# MainBoard_V100_PSU_AFE.net
KiCad netlist of a schematic drawn in Altium Designer
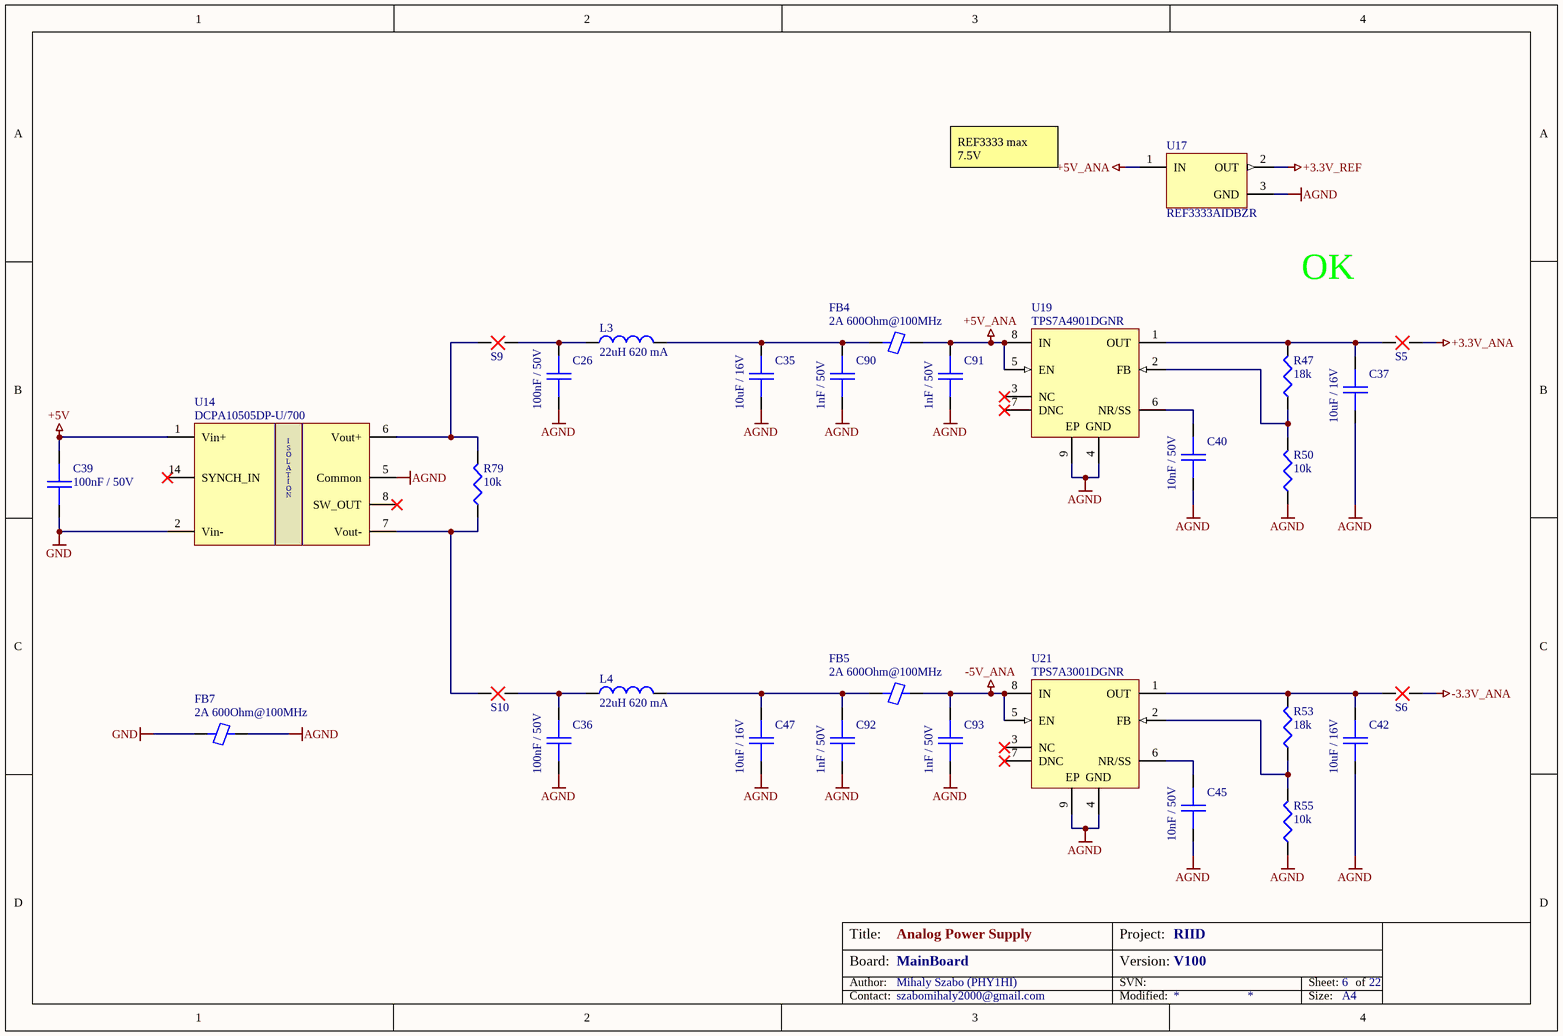
[diagram p0: MainBoard_V100_PSU_AFE.SchDoc]

(export (version "E")
  (design (tool "Eeschema 10.0.6"))
  (components
    (comp (ref "C26")
      (value "100nF / 50V")
      (footprint "0805_C")
      (description "100nF 50V X7R")
      (fields (field (name "PART NUMBER") "SMD0805-100nF-50V"))
      (libsource (lib "ALTIUM_DB_LIB") (part "CAP_NONPOL"))
    )
    (comp (ref "C35")
      (value "10uF / 16V")
      (footprint "0805_C")
      (description "10uF 16V X5R")
      (fields (field (name "PART NUMBER") "SMD0805-10uF-16V"))
      (libsource (lib "ALTIUM_DB_LIB") (part "CAP_NONPOL"))
    )
    (comp (ref "C36")
      (value "100nF / 50V")
      (footprint "0805_C")
      (description "100nF 50V X7R")
      (fields (field (name "PART NUMBER") "SMD0805-100nF-50V"))
      (libsource (lib "ALTIUM_DB_LIB") (part "CAP_NONPOL"))
    )
    (comp (ref "C37")
      (value "10uF / 16V")
      (footprint "0805_C")
      (description "10uF 16V X5R")
      (fields (field (name "PART NUMBER") "SMD0805-10uF-16V"))
      (libsource (lib "ALTIUM_DB_LIB") (part "CAP_NONPOL"))
    )
    (comp (ref "C39")
      (value "100nF / 50V")
      (footprint "0805_C")
      (description "100nF 50V X7R")
      (fields (field (name "PART NUMBER") "SMD0805-100nF-50V"))
      (libsource (lib "ALTIUM_DB_LIB") (part "CAP_NONPOL"))
    )
    (comp (ref "C40")
      (value "10nF / 50V")
      (footprint "0805_C")
      (description "10nF 50V X7R")
      (fields (field (name "PART NUMBER") "SMD0805-10nF-50V"))
      (libsource (lib "ALTIUM_DB_LIB") (part "CAP_NONPOL"))
    )
    (comp (ref "C42")
      (value "10uF / 16V")
      (footprint "0805_C")
      (description "10uF 16V X5R")
      (fields (field (name "PART NUMBER") "SMD0805-10uF-16V"))
      (libsource (lib "ALTIUM_DB_LIB") (part "CAP_NONPOL"))
    )
    (comp (ref "C45")
      (value "10nF / 50V")
      (footprint "0805_C")
      (description "10nF 50V X7R")
      (fields (field (name "PART NUMBER") "SMD0805-10nF-50V"))
      (libsource (lib "ALTIUM_DB_LIB") (part "CAP_NONPOL"))
    )
    (comp (ref "C47")
      (value "10uF / 16V")
      (footprint "0805_C")
      (description "10uF 16V X5R")
      (fields (field (name "PART NUMBER") "SMD0805-10uF-16V"))
      (libsource (lib "ALTIUM_DB_LIB") (part "CAP_NONPOL"))
    )
    (comp (ref "C90")
      (value "1nF / 50V")
      (footprint "0805_C")
      (description "1nF 50V X7R")
      (fields (field (name "PART NUMBER") "SMD0805-1nF-50V"))
      (libsource (lib "ALTIUM_DB_LIB") (part "CAP_NONPOL"))
    )
    (comp (ref "C91")
      (value "1nF / 50V")
      (footprint "0805_C")
      (description "1nF 50V X7R")
      (fields (field (name "PART NUMBER") "SMD0805-1nF-50V"))
      (libsource (lib "ALTIUM_DB_LIB") (part "CAP_NONPOL"))
    )
    (comp (ref "C92")
      (value "1nF / 50V")
      (footprint "0805_C")
      (description "1nF 50V X7R")
      (fields (field (name "PART NUMBER") "SMD0805-1nF-50V"))
      (libsource (lib "ALTIUM_DB_LIB") (part "CAP_NONPOL"))
    )
    (comp (ref "C93")
      (value "1nF / 50V")
      (footprint "0805_C")
      (description "1nF 50V X7R")
      (fields (field (name "PART NUMBER") "SMD0805-1nF-50V"))
      (libsource (lib "ALTIUM_DB_LIB") (part "CAP_NONPOL"))
    )
    (comp (ref "FB4")
      (value "2A 600Ohm@100MHz")
      (footprint "0805_FB")
      (description "Ferrite bead 2A 600Ohm@100MHz")
      (fields (field (name "PART NUMBER") "LCBB-601 SMD"))
      (libsource (lib "ALTIUM_DB_LIB") (part "FERRITE_BEAD"))
    )
    (comp (ref "FB5")
      (value "2A 600Ohm@100MHz")
      (footprint "0805_FB")
      (description "Ferrite bead 2A 600Ohm@100MHz")
      (fields (field (name "PART NUMBER") "LCBB-601 SMD"))
      (libsource (lib "ALTIUM_DB_LIB") (part "FERRITE_BEAD"))
    )
    (comp (ref "FB7")
      (value "2A 600Ohm@100MHz")
      (footprint "0805_FB")
      (description "Ferrite bead 2A 600Ohm@100MHz")
      (fields (field (name "PART NUMBER") "LCBB-601 SMD"))
      (libsource (lib "ALTIUM_DB_LIB") (part "FERRITE_BEAD"))
    )
    (comp (ref "L3")
      (value "22uH 620 mA")
      (footprint "1210")
      (description "22uH 620 mA 1210")
      (fields (field (name "PART NUMBER") "CBC3225T220KR"))
      (libsource (lib "ALTIUM_DB_LIB") (part "INDUCTOR"))
    )
    (comp (ref "L4")
      (value "22uH 620 mA")
      (footprint "1210")
      (description "22uH 620 mA 1210")
      (fields (field (name "PART NUMBER") "CBC3225T220KR"))
      (libsource (lib "ALTIUM_DB_LIB") (part "INDUCTOR"))
    )
    (comp (ref "R47")
      (value "18k")
      (footprint "0805")
      (description "18k 0805 0.125W 1%")
      (fields (field (name "PART NUMBER") "SMD0805-18K-1%"))
      (libsource (lib "ALTIUM_DB_LIB") (part "RESISTOR"))
    )
    (comp (ref "R50")
      (value "10k")
      (footprint "0805")
      (description "10k 0805 0.125W 1%")
      (fields (field (name "PART NUMBER") "SMD0805-10k 1%"))
      (libsource (lib "ALTIUM_DB_LIB") (part "RESISTOR"))
    )
    (comp (ref "R53")
      (value "18k")
      (footprint "0805")
      (description "18k 0805 0.125W 1%")
      (fields (field (name "PART NUMBER") "SMD0805-18K-1%"))
      (libsource (lib "ALTIUM_DB_LIB") (part "RESISTOR"))
    )
    (comp (ref "R55")
      (value "10k")
      (footprint "0805")
      (description "10k 0805 0.125W 1%")
      (fields (field (name "PART NUMBER") "SMD0805-10k 1%"))
      (libsource (lib "ALTIUM_DB_LIB") (part "RESISTOR"))
    )
    (comp (ref "R79")
      (value "10k")
      (footprint "0805")
      (description "10k 0805 0.125W 1%")
      (fields (field (name "PART NUMBER") "SMD0805-10k 1%"))
      (libsource (lib "ALTIUM_DB_LIB") (part "RESISTOR"))
    )
    (comp (ref "S5")
      (value "SPLITER")
      (footprint "SPLITER2_30mil_9mil")
      (description "SPLITER2_30mil_9mil")
      (libsource (lib "ALTIUM_DB_LIB") (part "SPLITER"))
    )
    (comp (ref "S6")
      (value "SPLITER")
      (footprint "SPLITER2_30mil_9mil")
      (description "SPLITER2_30mil_9mil")
      (libsource (lib "ALTIUM_DB_LIB") (part "SPLITER"))
    )
    (comp (ref "S9")
      (value "SPLITER")
      (footprint "SPLITER2_30mil_9mil")
      (description "SPLITER2_30mil_9mil")
      (libsource (lib "ALTIUM_DB_LIB") (part "SPLITER"))
    )
    (comp (ref "S10")
      (value "SPLITER")
      (footprint "SPLITER2_30mil_9mil")
      (description "SPLITER2_30mil_9mil")
      (libsource (lib "ALTIUM_DB_LIB") (part "SPLITER"))
    )
    (comp (ref "U14")
      (value "DCPA10505DP-U/700")
      (footprint "SOP-7")
      (description "Isolated DC/DC Converter, Vin = 5V, Vout = +/-5V, 1W, Isolated Unregulated,  7-SOP")
      (libsource (lib "ALTIUM_DB_LIB") (part "DCPA10505DP"))
    )
    (comp (ref "U17")
      (value "REF3333AIDBZR")
      (footprint "SOT-23")
      (description "VOLTAGE REF, SERIES, 3.3V, SOT-23-3 ,0.15 %,30ppm/°C")
      (libsource (lib "ALTIUM_DB_LIB") (part "REF3333AIDBZR"))
    )
    (comp (ref "U19")
      (value "TPS7A4901DGNR")
      (footprint "MSOP-8 TP")
      (description "LDO Voltage Regulator, Adjustable, 3 V to 35 V in, 333 mV drop, 1.194 V to 33 V/150 mA out, MSOP-8")
      (libsource (lib "ALTIUM_DB_LIB") (part "TPS7Axx01DGNR"))
    )
    (comp (ref "U21")
      (value "TPS7A3001DGNR")
      (footprint "MSOP-8 TP")
      (description "LDO Voltage Regulators -3V to -36V,-200mA High PSRR, LDO Reg")
      (libsource (lib "ALTIUM_DB_LIB") (part "TPS7Axx01DGNR"))
    )
  )
  (nets
    (net (code "1") (name "+3.3V_ANA") (class "Default")
      (node (ref "S5") (pin "2") (pinfunction "2_2") (pintype "passive"))
    )
    (net (code "2") (name "+3.3V_REF") (class "Default")
      (node (ref "U17") (pin "2") (pinfunction "OUT_2") (pintype "output"))
    )
    (net (code "3") (name "+5V") (class "Default")
      (node (ref "C39") (pin "1") (pintype "passive"))
      (node (ref "U14") (pin "1") (pinfunction "Vin+_1") (pintype "passive"))
    )
    (net (code "4") (name "+5V_ANA") (class "Default")
      (node (ref "C91") (pin "1") (pintype "passive"))
      (node (ref "FB4") (pin "2") (pinfunction "2_2") (pintype "passive"))
      (node (ref "U17") (pin "1") (pinfunction "IN_1") (pintype "power_in"))
      (node (ref "U19") (pin "5") (pinfunction "EN_5") (pintype "input"))
      (node (ref "U19") (pin "8") (pinfunction "IN_8") (pintype "power_in"))
    )
    (net (code "5") (name "-3.3V_ANA") (class "Default")
      (node (ref "S6") (pin "2") (pinfunction "2_2") (pintype "passive"))
    )
    (net (code "6") (name "-5V_ANA") (class "Default")
      (node (ref "C93") (pin "1") (pintype "passive"))
      (node (ref "FB5") (pin "2") (pinfunction "2_2") (pintype "passive"))
      (node (ref "U21") (pin "5") (pinfunction "EN_5") (pintype "input"))
      (node (ref "U21") (pin "8") (pinfunction "IN_8") (pintype "power_in"))
    )
    (net (code "7") (name "AGND") (class "Default")
      (node (ref "C26") (pin "2") (pintype "passive"))
      (node (ref "C35") (pin "2") (pintype "passive"))
      (node (ref "C36") (pin "2") (pintype "passive"))
      (node (ref "C37") (pin "1") (pintype "passive"))
      (node (ref "C40") (pin "2") (pintype "passive"))
      (node (ref "C42") (pin "1") (pintype "passive"))
      (node (ref "C45") (pin "2") (pintype "passive"))
      (node (ref "C47") (pin "2") (pintype "passive"))
      (node (ref "C90") (pin "2") (pintype "passive"))
      (node (ref "C91") (pin "2") (pintype "passive"))
      (node (ref "C92") (pin "2") (pintype "passive"))
      (node (ref "C93") (pin "2") (pintype "passive"))
      (node (ref "FB7") (pin "2") (pinfunction "2_2") (pintype "passive"))
      (node (ref "R50") (pin "1") (pintype "passive"))
      (node (ref "R55") (pin "1") (pintype "passive"))
      (node (ref "U14") (pin "5") (pinfunction "Common_5") (pintype "passive"))
      (node (ref "U17") (pin "3") (pinfunction "GND_3") (pintype "power_in"))
      (node (ref "U19") (pin "4") (pinfunction "GND_4") (pintype "power_in"))
      (node (ref "U19") (pin "9") (pinfunction "EP_9") (pintype "passive"))
      (node (ref "U21") (pin "4") (pinfunction "GND_4") (pintype "power_in"))
      (node (ref "U21") (pin "9") (pinfunction "EP_9") (pintype "passive"))
    )
    (net (code "8") (name "GND") (class "Default")
      (node (ref "C39") (pin "2") (pintype "passive"))
      (node (ref "FB7") (pin "1") (pinfunction "1_1") (pintype "passive"))
      (node (ref "U14") (pin "2") (pinfunction "Vin-_2") (pintype "passive"))
    )
    (net (code "9") (name "Net-(C26-Pad1)") (class "Default")
      (node (ref "C26") (pin "1") (pintype "passive"))
      (node (ref "L3") (pin "1") (pinfunction "1_1") (pintype "passive"))
      (node (ref "S9") (pin "2") (pinfunction "2_2") (pintype "passive"))
    )
    (net (code "10") (name "Net-(C35-Pad1)") (class "Default")
      (node (ref "C35") (pin "1") (pintype "passive"))
      (node (ref "C90") (pin "1") (pintype "passive"))
      (node (ref "FB4") (pin "1") (pinfunction "1_1") (pintype "passive"))
      (node (ref "L3") (pin "2") (pinfunction "2_2") (pintype "passive"))
    )
    (net (code "11") (name "Net-(C36-Pad1)") (class "Default")
      (node (ref "C36") (pin "1") (pintype "passive"))
      (node (ref "L4") (pin "1") (pinfunction "1_1") (pintype "passive"))
      (node (ref "S10") (pin "2") (pinfunction "2_2") (pintype "passive"))
    )
    (net (code "12") (name "Net-(C47-Pad1)") (class "Default")
      (node (ref "C47") (pin "1") (pintype "passive"))
      (node (ref "C92") (pin "1") (pintype "passive"))
      (node (ref "FB5") (pin "1") (pinfunction "1_1") (pintype "passive"))
      (node (ref "L4") (pin "2") (pinfunction "2_2") (pintype "passive"))
    )
    (net (code "13") (name "Net-(U14-Vout+)") (class "Default")
      (node (ref "R79") (pin "2") (pintype "passive"))
      (node (ref "S9") (pin "1") (pinfunction "1_1") (pintype "passive"))
      (node (ref "U14") (pin "6") (pinfunction "Vout+_6") (pintype "passive"))
    )
    (net (code "14") (name "Net-(U14-Vout-)") (class "Default")
      (node (ref "R79") (pin "1") (pintype "passive"))
      (node (ref "S10") (pin "1") (pinfunction "1_1") (pintype "passive"))
      (node (ref "U14") (pin "7") (pinfunction "Vout-_7") (pintype "passive"))
    )
    (net (code "15") (name "Net-(U19-FB)") (class "Default")
      (node (ref "R47") (pin "1") (pintype "passive"))
      (node (ref "R50") (pin "2") (pintype "passive"))
      (node (ref "U19") (pin "2") (pinfunction "FB_2") (pintype "input"))
    )
    (net (code "16") (name "Net-(U19-NR{slash}SS)") (class "Default")
      (node (ref "C40") (pin "1") (pintype "passive"))
      (node (ref "U19") (pin "6") (pinfunction "NR/SS_6") (pintype "passive"))
    )
    (net (code "17") (name "Net-(U19-OUT)") (class "Default")
      (node (ref "C37") (pin "2") (pintype "passive"))
      (node (ref "R47") (pin "2") (pintype "passive"))
      (node (ref "S5") (pin "1") (pinfunction "1_1") (pintype "passive"))
      (node (ref "U19") (pin "1") (pinfunction "OUT_1") (pintype "power_in"))
    )
    (net (code "18") (name "Net-(U21-FB)") (class "Default")
      (node (ref "R53") (pin "1") (pintype "passive"))
      (node (ref "R55") (pin "2") (pintype "passive"))
      (node (ref "U21") (pin "2") (pinfunction "FB_2") (pintype "input"))
    )
    (net (code "19") (name "Net-(U21-NR{slash}SS)") (class "Default")
      (node (ref "C45") (pin "1") (pintype "passive"))
      (node (ref "U21") (pin "6") (pinfunction "NR/SS_6") (pintype "passive"))
    )
    (net (code "20") (name "Net-(U21-OUT)") (class "Default")
      (node (ref "C42") (pin "2") (pintype "passive"))
      (node (ref "R53") (pin "2") (pintype "passive"))
      (node (ref "S6") (pin "1") (pinfunction "1_1") (pintype "passive"))
      (node (ref "U21") (pin "1") (pinfunction "OUT_1") (pintype "power_in"))
    )
    (net (code "21") (name "unconnected-(U14-SW_OUT-Pad8)") (class "Default")
      (node (ref "U14") (pin "8") (pinfunction "SW_OUT_8") (pintype "passive+no_connect"))
    )
    (net (code "22") (name "unconnected-(U14-SYNCH_IN-Pad14)") (class "Default")
      (node (ref "U14") (pin "14") (pinfunction "SYNCH_IN_14") (pintype "passive+no_connect"))
    )
    (net (code "23") (name "unconnected-(U19-DNC-Pad7)") (class "Default")
      (node (ref "U19") (pin "7") (pinfunction "DNC_7") (pintype "passive+no_connect"))
    )
    (net (code "24") (name "unconnected-(U19-NC-Pad3)") (class "Default")
      (node (ref "U19") (pin "3") (pinfunction "NC_3") (pintype "passive+no_connect"))
    )
    (net (code "25") (name "unconnected-(U21-DNC-Pad7)") (class "Default")
      (node (ref "U21") (pin "7") (pinfunction "DNC_7") (pintype "passive+no_connect"))
    )
    (net (code "26") (name "unconnected-(U21-NC-Pad3)") (class "Default")
      (node (ref "U21") (pin "3") (pinfunction "NC_3") (pintype "passive+no_connect"))
    )
  )
)
